# tx.net
KiCad netlist of a schematic drawn in EAGLE
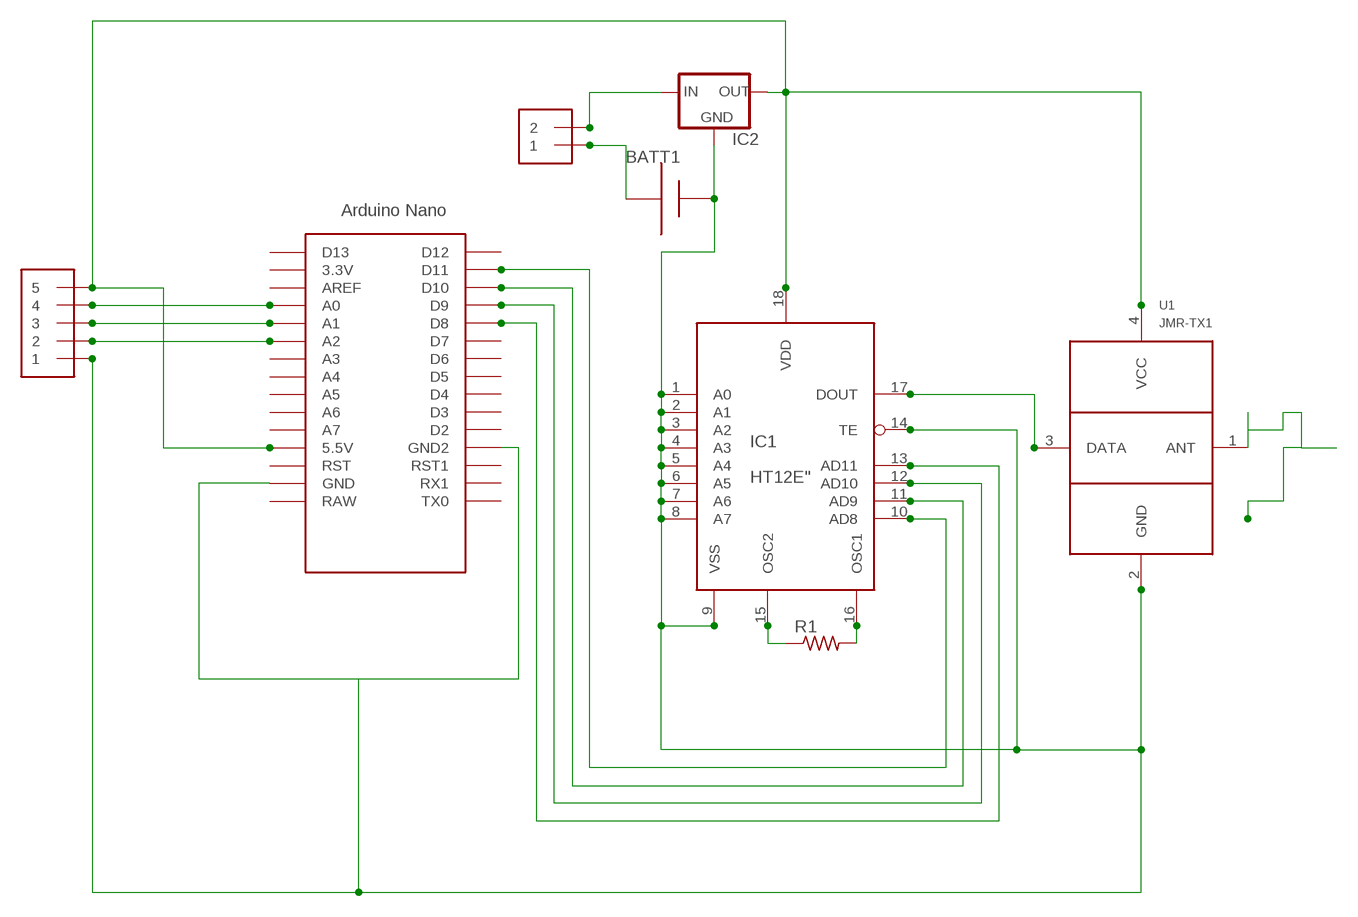
[diagram p0: schematic, sheet 1]

(export (version "E")
  (design (tool "Eeschema 10.0.6"))
  (components
    (comp (ref "BATT1")
      (value "AAA")
      (footprint "eagle-import:12BH412")
      (libsource (lib "eagle-import") (part "AAA"))
    )
    (comp (ref "IC1")
      (value "HT12E\"")
      (footprint "eagle-import:18-DIP-A")
      (libsource (lib "eagle-import") (part "HT12E{dblquote}"))
    )
    (comp (ref "IC2")
      (value "78MXXL")
      (footprint "eagle-import:78MXXL")
      (libsource (lib "eagle-import") (part "78MXXL"))
    )
    (comp (ref "J1")
      (value "1X5")
      (footprint "eagle-import:1X05-3.5MM")
      (libsource (lib "eagle-import") (part "1X5"))
    )
    (comp (ref "J2")
      (value "1X2-3.5MM")
      (footprint "eagle-import:1X2-3.5MM")
      (libsource (lib "eagle-import") (part "1X2-3.5MM"))
    )
    (comp (ref "R1")
      (value "R-US_0207/9")
      (footprint "eagle-import:0207_9")
      (libsource (lib "eagle-import") (part "R-US_0207/9"))
    )
    (comp (ref "U$2")
      (value "NANO")
      (footprint "eagle-import:NANO")
      (libsource (lib "eagle-import") (part "NANO"))
    )
    (comp (ref "U1")
      (value "JMR-TX1")
      (footprint "eagle-import:JMR-TX1")
      (libsource (lib "eagle-import") (part "JMR-TX1"))
    )
  )
  (nets
    (net (code "1") (name "Net-(BATT1-Pad-)") (class "Default")
      (node (ref "BATT1") (pin "-") (pinfunction "-_-") (pintype "bidirectional"))
      (node (ref "J2") (pin "1") (pinfunction "1_1") (pintype "passive"))
    )
    (net (code "2") (name "Net-(IC1-A0)") (class "Default")
      (node (ref "BATT1") (pin "+") (pinfunction "+_+") (pintype "bidirectional"))
      (node (ref "IC1") (pin "1") (pinfunction "A0_1") (pintype "input"))
      (node (ref "IC1") (pin "14") (pinfunction "TE_14") (pintype "power_in"))
      (node (ref "IC1") (pin "2") (pinfunction "A1_2") (pintype "input"))
      (node (ref "IC1") (pin "3") (pinfunction "A2_3") (pintype "input"))
      (node (ref "IC1") (pin "4") (pinfunction "A3_4") (pintype "input"))
      (node (ref "IC1") (pin "5") (pinfunction "A4_5") (pintype "input"))
      (node (ref "IC1") (pin "6") (pinfunction "A5_6") (pintype "input"))
      (node (ref "IC1") (pin "7") (pinfunction "A6_7") (pintype "input"))
      (node (ref "IC1") (pin "8") (pinfunction "A7_8") (pintype "input"))
      (node (ref "IC1") (pin "9") (pinfunction "VSS_9") (pintype "power_in"))
      (node (ref "IC2") (pin "GND") (pinfunction "GND_GND") (pintype "input"))
      (node (ref "J1") (pin "1") (pinfunction "1_1") (pintype "passive"))
      (node (ref "U$2") (pin "GND") (pinfunction "GND_GND") (pintype "bidirectional"))
      (node (ref "U$2") (pin "GND1") (pinfunction "GND2_GND1") (pintype "bidirectional"))
      (node (ref "U1") (pin "2") (pinfunction "GND_2") (pintype "power_in"))
    )
    (net (code "3") (name "Net-(IC1-AD8)") (class "Default")
      (node (ref "IC1") (pin "10") (pinfunction "AD8_10") (pintype "input"))
      (node (ref "U$2") (pin "D11") (pinfunction "D11_D11") (pintype "bidirectional"))
    )
    (net (code "4") (name "Net-(IC1-AD9)") (class "Default")
      (node (ref "IC1") (pin "11") (pinfunction "AD9_11") (pintype "input"))
      (node (ref "U$2") (pin "D10") (pinfunction "D10_D10") (pintype "bidirectional"))
    )
    (net (code "5") (name "Net-(IC1-AD10)") (class "Default")
      (node (ref "IC1") (pin "12") (pinfunction "AD10_12") (pintype "input"))
      (node (ref "U$2") (pin "D9") (pinfunction "D9_D9") (pintype "bidirectional"))
    )
    (net (code "6") (name "Net-(IC1-AD11)") (class "Default")
      (node (ref "IC1") (pin "13") (pinfunction "AD11_13") (pintype "input"))
      (node (ref "U$2") (pin "D8") (pinfunction "D8_D8") (pintype "bidirectional"))
    )
    (net (code "7") (name "Net-(IC1-DOUT)") (class "Default")
      (node (ref "IC1") (pin "17") (pinfunction "DOUT_17") (pintype "output"))
      (node (ref "U1") (pin "3") (pinfunction "DATA_3") (pintype "input"))
    )
    (net (code "8") (name "Net-(IC1-OSC1)") (class "Default")
      (node (ref "IC1") (pin "16") (pinfunction "OSC1_16") (pintype "input"))
      (node (ref "R1") (pin "2") (pinfunction "2_2") (pintype "passive"))
    )
    (net (code "9") (name "Net-(IC1-OSC2)") (class "Default")
      (node (ref "IC1") (pin "15") (pinfunction "OSC2_15") (pintype "input"))
      (node (ref "R1") (pin "1") (pinfunction "1_1") (pintype "passive"))
    )
    (net (code "10") (name "Net-(IC1-VDD)") (class "Default")
      (node (ref "IC1") (pin "18") (pinfunction "VDD_18") (pintype "power_in"))
      (node (ref "IC2") (pin "OUT") (pinfunction "OUT_OUT") (pintype "passive"))
      (node (ref "J1") (pin "5") (pinfunction "5_5") (pintype "passive"))
      (node (ref "U$2") (pin "5V") (pinfunction "5.5V_5V") (pintype "bidirectional"))
      (node (ref "U1") (pin "4") (pinfunction "VCC_4") (pintype "power_in"))
    )
    (net (code "11") (name "Net-(IC2-PadIN)") (class "Default")
      (node (ref "IC2") (pin "IN") (pinfunction "IN_IN") (pintype "input"))
      (node (ref "J2") (pin "2") (pinfunction "2_2") (pintype "passive"))
    )
    (net (code "12") (name "Net-(J1-Pad2)") (class "Default")
      (node (ref "J1") (pin "2") (pinfunction "2_2") (pintype "passive"))
      (node (ref "U$2") (pin "A2") (pinfunction "A2_A2") (pintype "bidirectional"))
    )
    (net (code "13") (name "Net-(J1-Pad3)") (class "Default")
      (node (ref "J1") (pin "3") (pinfunction "3_3") (pintype "passive"))
      (node (ref "U$2") (pin "A1") (pinfunction "A1_A1") (pintype "bidirectional"))
    )
    (net (code "14") (name "Net-(J1-Pad4)") (class "Default")
      (node (ref "J1") (pin "4") (pinfunction "4_4") (pintype "passive"))
      (node (ref "U$2") (pin "A0") (pinfunction "A0_A0") (pintype "bidirectional"))
    )
    (net (code "15") (name "unconnected-(U$2-Pad3.3V)") (class "Default")
      (node (ref "U$2") (pin "3.3V") (pinfunction "3.3V_3.3V") (pintype "bidirectional"))
    )
    (net (code "16") (name "unconnected-(U$2-PadA3)") (class "Default")
      (node (ref "U$2") (pin "A3") (pinfunction "A3_A3") (pintype "bidirectional"))
    )
    (net (code "17") (name "unconnected-(U$2-PadA4)") (class "Default")
      (node (ref "U$2") (pin "A4") (pinfunction "A4_A4") (pintype "bidirectional"))
    )
    (net (code "18") (name "unconnected-(U$2-PadA5)") (class "Default")
      (node (ref "U$2") (pin "A5") (pinfunction "A5_A5") (pintype "bidirectional"))
    )
    (net (code "19") (name "unconnected-(U$2-PadA6)") (class "Default")
      (node (ref "U$2") (pin "A6") (pinfunction "A6_A6") (pintype "bidirectional"))
    )
    (net (code "20") (name "unconnected-(U$2-PadA7)") (class "Default")
      (node (ref "U$2") (pin "A7") (pinfunction "A7_A7") (pintype "bidirectional"))
    )
    (net (code "21") (name "unconnected-(U$2-PadAREF)") (class "Default")
      (node (ref "U$2") (pin "AREF") (pinfunction "AREF_AREF") (pintype "bidirectional"))
    )
    (net (code "22") (name "unconnected-(U$2-PadD2)") (class "Default")
      (node (ref "U$2") (pin "D2") (pinfunction "D2_D2") (pintype "bidirectional"))
    )
    (net (code "23") (name "unconnected-(U$2-PadD3)") (class "Default")
      (node (ref "U$2") (pin "D3") (pinfunction "D3_D3") (pintype "bidirectional"))
    )
    (net (code "24") (name "unconnected-(U$2-PadD4)") (class "Default")
      (node (ref "U$2") (pin "D4") (pinfunction "D4_D4") (pintype "bidirectional"))
    )
    (net (code "25") (name "unconnected-(U$2-PadD5)") (class "Default")
      (node (ref "U$2") (pin "D5") (pinfunction "D5_D5") (pintype "bidirectional"))
    )
    (net (code "26") (name "unconnected-(U$2-PadD6)") (class "Default")
      (node (ref "U$2") (pin "D6") (pinfunction "D6_D6") (pintype "bidirectional"))
    )
    (net (code "27") (name "unconnected-(U$2-PadD7)") (class "Default")
      (node (ref "U$2") (pin "D7") (pinfunction "D7_D7") (pintype "bidirectional"))
    )
    (net (code "28") (name "unconnected-(U$2-PadD12)") (class "Default")
      (node (ref "U$2") (pin "D12") (pinfunction "D12_D12") (pintype "bidirectional"))
    )
    (net (code "29") (name "unconnected-(U$2-PadD13)") (class "Default")
      (node (ref "U$2") (pin "D13") (pinfunction "D13_D13") (pintype "bidirectional"))
    )
    (net (code "30") (name "unconnected-(U$2-PadICSP1)") (class "Default")
      (node (ref "U$2") (pin "ICSP1") (pinfunction "ICSP1_ICSP1") (pintype "bidirectional"))
    )
    (net (code "31") (name "unconnected-(U$2-PadICSP2)") (class "Default")
      (node (ref "U$2") (pin "ICSP2") (pinfunction "ICSP2_ICSP2") (pintype "bidirectional"))
    )
    (net (code "32") (name "unconnected-(U$2-PadICSP3)") (class "Default")
      (node (ref "U$2") (pin "ICSP3") (pinfunction "ICSP3_ICSP3") (pintype "bidirectional"))
    )
    (net (code "33") (name "unconnected-(U$2-PadICSP4)") (class "Default")
      (node (ref "U$2") (pin "ICSP4") (pinfunction "ICSP4_ICSP4") (pintype "bidirectional"))
    )
    (net (code "34") (name "unconnected-(U$2-PadICSP5)") (class "Default")
      (node (ref "U$2") (pin "ICSP5") (pinfunction "ICSP5_ICSP5") (pintype "bidirectional"))
    )
    (net (code "35") (name "unconnected-(U$2-PadICSP6)") (class "Default")
      (node (ref "U$2") (pin "ICSP6") (pinfunction "ICSP6_ICSP6") (pintype "bidirectional"))
    )
    (net (code "36") (name "unconnected-(U$2-PadRAW)") (class "Default")
      (node (ref "U$2") (pin "RAW") (pinfunction "RAW_RAW") (pintype "bidirectional"))
    )
    (net (code "37") (name "unconnected-(U$2-PadRST)") (class "Default")
      (node (ref "U$2") (pin "RST") (pinfunction "RST_RST") (pintype "bidirectional"))
    )
    (net (code "38") (name "unconnected-(U$2-PadRST1)") (class "Default")
      (node (ref "U$2") (pin "RST1") (pinfunction "RST1_RST1") (pintype "bidirectional"))
    )
    (net (code "39") (name "unconnected-(U$2-PadRX1)") (class "Default")
      (node (ref "U$2") (pin "RX1") (pinfunction "RX1_RX1") (pintype "bidirectional"))
    )
    (net (code "40") (name "unconnected-(U$2-PadTX0)") (class "Default")
      (node (ref "U$2") (pin "TX0") (pinfunction "TX0_TX0") (pintype "bidirectional"))
    )
    (net (code "41") (name "unconnected-(U1-ANT-Pad1)") (class "Default")
      (node (ref "U1") (pin "1") (pinfunction "ANT_1") (pintype "output"))
    )
  )
)
